# midithru.net
KiCad netlist of a schematic drawn in Altium Designer
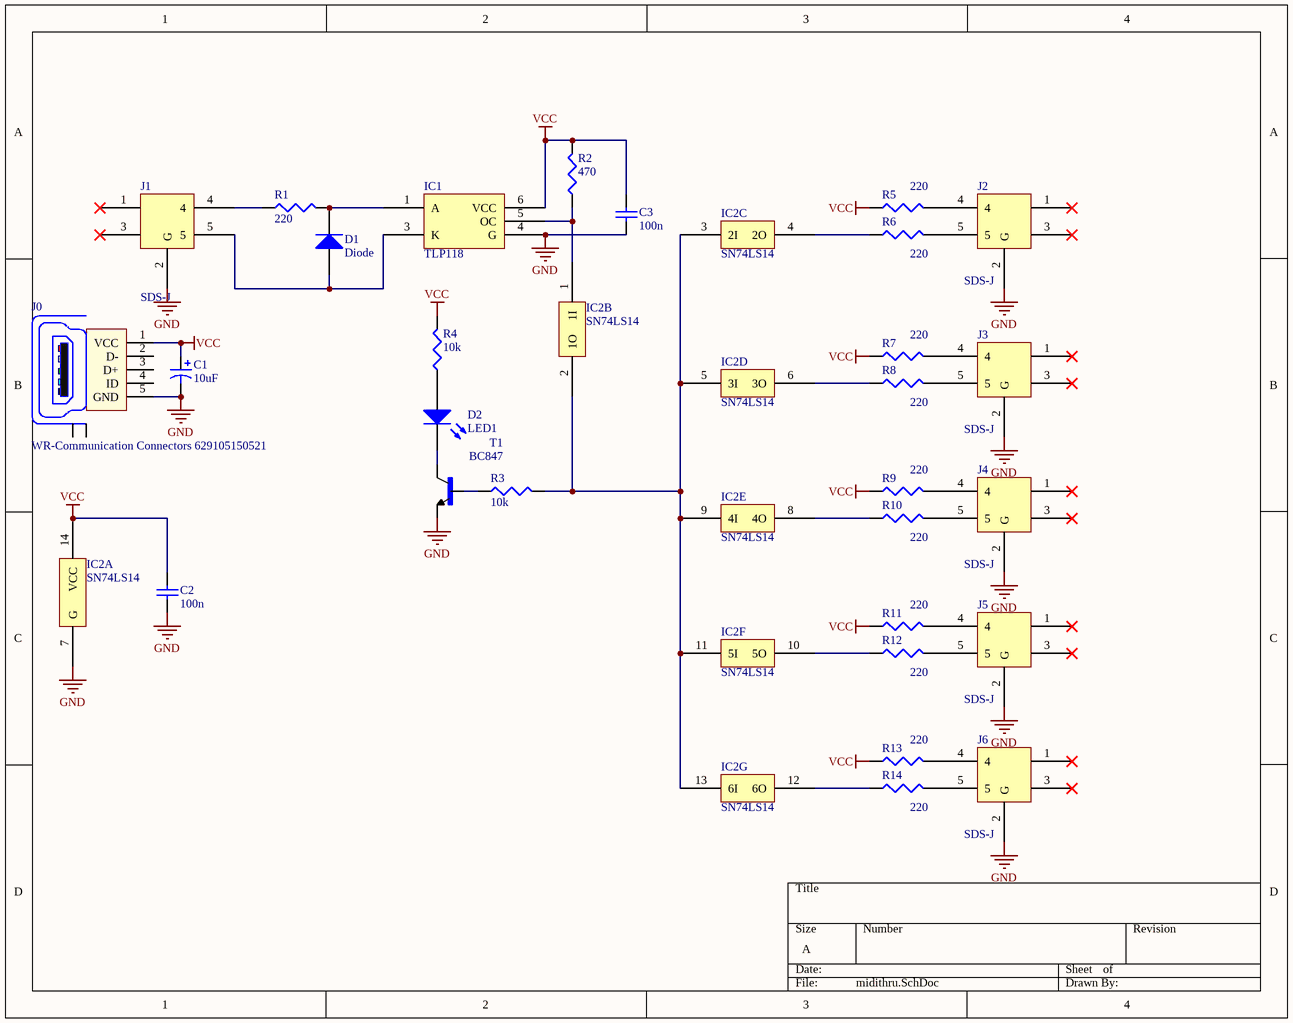
[diagram p0: midithru.SchDoc]

(export (version "E")
  (design (tool "Eeschema 10.0.6"))
  (components
    (comp (ref "C1")
      (value "10uF")
      (footprint "1210")
      (description "Polarized Capacitor (Surface Mount)")
      (fields (field (name "PUBLISHER") "Altium Limited"))
      (libsource (lib "Miscellaneous Devices") (part "Cap Pol3"))
    )
    (comp (ref "C2")
      (value "100n")
      (footprint "0805")
      (description "Capacitor (Semiconductor SIM Model)")
      (fields (field (name "PUBLISHER") "Altium Limited"))
      (libsource (lib "Miscellaneous Devices") (part "Cap Semi"))
    )
    (comp (ref "C3")
      (value "100n")
      (footprint "0805")
      (description "Capacitor (Semiconductor SIM Model)")
      (fields (field (name "PUBLISHER") "Altium Limited"))
      (libsource (lib "Miscellaneous Devices") (part "Cap Semi"))
    )
    (comp (ref "D1")
      (value "Diode")
      (footprint "0805")
      (description "Default Diode")
      (fields (field (name "PUBLISHER") "Altium Limited"))
      (libsource (lib "Miscellaneous Devices") (part "Diode"))
    )
    (comp (ref "D2")
      (value "LED1")
      (footprint "3.2X1.6X1.1")
      (description "Typical RED, GREEN, YELLOW, AMBER GaAs LED")
      (fields (field (name "PUBLISHER") "Altium Limited"))
      (libsource (lib "Miscellaneous Devices") (part "LED2"))
    )
    (comp (ref "IC1") (value "TLP118") (footprint "SOIC6") (libsource (lib "schlib") (part "TLP118")))
    (comp (ref "IC2") (value "SN74LS14") (footprint "SOIC14") (libsource (lib "schlib") (part "SN74LS14")))
    (comp (ref "J0")
      (value "WR-Communication Connectors 629105150521")
      (footprint "629105150521")
      (description "WR-COM_USB_Micro Type B_Horizontal_SMT")
      (fields
        (field (name "MANUFACTURER") "Würth Elektronik eiSos GmbH")
        (field (name "PARTNO") "629105150521")
        (field (name "CREATED BY") "Karrer Zheng")
      )
      (libsource (lib "629105136821 (rev16d)") (part "WR-Communication Connectors 629105150521"))
    )
    (comp (ref "J1") (value "SDS-J") (footprint "SDS-J") (libsource (lib "") (part "SDS-J_1")))
    (comp (ref "J2") (value "SDS-J") (footprint "SDS-J") (libsource (lib "schlib") (part "SDS-J")))
    (comp (ref "J3") (value "SDS-J") (footprint "SDS-J") (libsource (lib "schlib") (part "SDS-J")))
    (comp (ref "J4") (value "SDS-J") (footprint "SDS-J") (libsource (lib "schlib") (part "SDS-J")))
    (comp (ref "J5") (value "SDS-J") (footprint "SDS-J") (libsource (lib "schlib") (part "SDS-J")))
    (comp (ref "J6") (value "SDS-J") (footprint "SDS-J") (libsource (lib "schlib") (part "SDS-J")))
    (comp (ref "R1")
      (value "220")
      (footprint "0805")
      (description "Resistor")
      (fields (field (name "PUBLISHER") "Altium Limited"))
      (libsource (lib "Miscellaneous Devices") (part "Res3"))
    )
    (comp (ref "R2")
      (value "470")
      (footprint "0805")
      (description "Resistor")
      (fields (field (name "PUBLISHER") "Altium Limited"))
      (libsource (lib "Miscellaneous Devices") (part "Res3"))
    )
    (comp (ref "R3")
      (value "10k")
      (footprint "0805")
      (description "Resistor")
      (fields (field (name "PUBLISHER") "Altium Limited"))
      (libsource (lib "Miscellaneous Devices") (part "Res3"))
    )
    (comp (ref "R4")
      (value "10k")
      (footprint "0805")
      (description "Resistor")
      (fields (field (name "PUBLISHER") "Altium Limited"))
      (libsource (lib "Miscellaneous Devices") (part "Res3"))
    )
    (comp (ref "R5")
      (value "220")
      (footprint "0805")
      (description "Resistor")
      (fields (field (name "PUBLISHER") "Altium Limited"))
      (libsource (lib "Miscellaneous Devices") (part "Res3"))
    )
    (comp (ref "R6")
      (value "220")
      (footprint "0805")
      (description "Resistor")
      (fields (field (name "PUBLISHER") "Altium Limited"))
      (libsource (lib "Miscellaneous Devices") (part "Res3"))
    )
    (comp (ref "R7")
      (value "220")
      (footprint "0805")
      (description "Resistor")
      (fields (field (name "PUBLISHER") "Altium Limited"))
      (libsource (lib "Miscellaneous Devices") (part "Res3"))
    )
    (comp (ref "R8")
      (value "220")
      (footprint "0805")
      (description "Resistor")
      (fields (field (name "PUBLISHER") "Altium Limited"))
      (libsource (lib "Miscellaneous Devices") (part "Res3"))
    )
    (comp (ref "R9")
      (value "220")
      (footprint "0805")
      (description "Resistor")
      (fields (field (name "PUBLISHER") "Altium Limited"))
      (libsource (lib "Miscellaneous Devices") (part "Res3"))
    )
    (comp (ref "R10")
      (value "220")
      (footprint "0805")
      (description "Resistor")
      (fields (field (name "PUBLISHER") "Altium Limited"))
      (libsource (lib "Miscellaneous Devices") (part "Res3"))
    )
    (comp (ref "R11")
      (value "220")
      (footprint "0805")
      (description "Resistor")
      (fields (field (name "PUBLISHER") "Altium Limited"))
      (libsource (lib "Miscellaneous Devices") (part "Res3"))
    )
    (comp (ref "R12")
      (value "220")
      (footprint "0805")
      (description "Resistor")
      (fields (field (name "PUBLISHER") "Altium Limited"))
      (libsource (lib "Miscellaneous Devices") (part "Res3"))
    )
    (comp (ref "R13")
      (value "220")
      (footprint "0805")
      (description "Resistor")
      (fields (field (name "PUBLISHER") "Altium Limited"))
      (libsource (lib "Miscellaneous Devices") (part "Res3"))
    )
    (comp (ref "R14")
      (value "220")
      (footprint "0805")
      (description "Resistor")
      (fields (field (name "PUBLISHER") "Altium Limited"))
      (libsource (lib "Miscellaneous Devices") (part "Res3"))
    )
    (comp (ref "T1")
      (value "BC847")
      (footprint "*SOT23")
      (fields (field (name "MF") "Nexperia USA"))
      (libsource (lib "BC847") (part "BC847"))
    )
  )
  (nets
    (net (code "1") (name "GND") (class "Default")
      (node (ref "C1") (pin "2") (pinfunction "2_2") (pintype "passive"))
      (node (ref "C2") (pin "2") (pinfunction "2_2") (pintype "passive"))
      (node (ref "C3") (pin "2") (pinfunction "2_2") (pintype "passive"))
      (node (ref "IC1") (pin "4") (pinfunction "G_4") (pintype "passive"))
      (node (ref "IC2") (pin "7") (pinfunction "G_7") (pintype "passive"))
      (node (ref "J0") (pin "5") (pinfunction "GND_5") (pintype "passive"))
      (node (ref "J1") (pin "2") (pinfunction "G_2") (pintype "passive"))
      (node (ref "J2") (pin "2") (pinfunction "G_2") (pintype "passive"))
      (node (ref "J3") (pin "2") (pinfunction "G_2") (pintype "passive"))
      (node (ref "J4") (pin "2") (pinfunction "G_2") (pintype "passive"))
      (node (ref "J5") (pin "2") (pinfunction "G_2") (pintype "passive"))
      (node (ref "J6") (pin "2") (pinfunction "G_2") (pintype "passive"))
      (node (ref "T1") (pin "2") (pinfunction "E_2") (pintype "passive"))
    )
    (net (code "2") (name "Net-(D1-A)") (class "Default")
      (node (ref "D1") (pin "1") (pinfunction "A_1") (pintype "passive"))
      (node (ref "IC1") (pin "3") (pinfunction "K_3") (pintype "passive"))
      (node (ref "J1") (pin "5") (pinfunction "5_5") (pintype "passive"))
    )
    (net (code "3") (name "Net-(D1-K)") (class "Default")
      (node (ref "D1") (pin "2") (pinfunction "K_2") (pintype "passive"))
      (node (ref "IC1") (pin "1") (pinfunction "A_1") (pintype "passive"))
      (node (ref "R1") (pin "2") (pinfunction "2_2") (pintype "passive"))
    )
    (net (code "4") (name "Net-(D2-A)") (class "Default")
      (node (ref "D2") (pin "1") (pinfunction "A_1") (pintype "passive"))
      (node (ref "R4") (pin "1") (pinfunction "1_1") (pintype "passive"))
    )
    (net (code "5") (name "Net-(D2-K)") (class "Default")
      (node (ref "D2") (pin "2") (pinfunction "K_2") (pintype "passive"))
      (node (ref "T1") (pin "3") (pinfunction "C_3") (pintype "passive"))
    )
    (net (code "6") (name "Net-(IC1-OC)") (class "Default")
      (node (ref "IC1") (pin "5") (pinfunction "OC_5") (pintype "passive"))
      (node (ref "IC2") (pin "1") (pinfunction "1I_1") (pintype "passive"))
      (node (ref "R2") (pin "1") (pinfunction "1_1") (pintype "passive"))
    )
    (net (code "7") (name "Net-(IC2B-1O)") (class "Default")
      (node (ref "IC2") (pin "11") (pinfunction "5I_11") (pintype "passive"))
      (node (ref "IC2") (pin "13") (pinfunction "6I_13") (pintype "passive"))
      (node (ref "IC2") (pin "2") (pinfunction "1O_2") (pintype "passive"))
      (node (ref "IC2") (pin "3") (pinfunction "2I_3") (pintype "passive"))
      (node (ref "IC2") (pin "5") (pinfunction "3I_5") (pintype "passive"))
      (node (ref "IC2") (pin "9") (pinfunction "4I_9") (pintype "passive"))
      (node (ref "R3") (pin "2") (pinfunction "2_2") (pintype "passive"))
    )
    (net (code "8") (name "Net-(IC2C-2O)") (class "Default")
      (node (ref "IC2") (pin "4") (pinfunction "2O_4") (pintype "passive"))
      (node (ref "R6") (pin "1") (pinfunction "1_1") (pintype "passive"))
    )
    (net (code "9") (name "Net-(IC2D-3O)") (class "Default")
      (node (ref "IC2") (pin "6") (pinfunction "3O_6") (pintype "passive"))
      (node (ref "R8") (pin "1") (pinfunction "1_1") (pintype "passive"))
    )
    (net (code "10") (name "Net-(IC2E-4O)") (class "Default")
      (node (ref "IC2") (pin "8") (pinfunction "4O_8") (pintype "passive"))
      (node (ref "R10") (pin "1") (pinfunction "1_1") (pintype "passive"))
    )
    (net (code "11") (name "Net-(IC2F-5O)") (class "Default")
      (node (ref "IC2") (pin "10") (pinfunction "5O_10") (pintype "passive"))
      (node (ref "R12") (pin "1") (pinfunction "1_1") (pintype "passive"))
    )
    (net (code "12") (name "Net-(IC2G-6O)") (class "Default")
      (node (ref "IC2") (pin "12") (pinfunction "6O_12") (pintype "passive"))
      (node (ref "R14") (pin "1") (pinfunction "1_1") (pintype "passive"))
    )
    (net (code "13") (name "Net-(J1-Pad4)") (class "Default")
      (node (ref "J1") (pin "4") (pinfunction "4_4") (pintype "passive"))
      (node (ref "R1") (pin "1") (pinfunction "1_1") (pintype "passive"))
    )
    (net (code "14") (name "Net-(J2-Pad4)") (class "Default")
      (node (ref "J2") (pin "4") (pinfunction "4_4") (pintype "passive"))
      (node (ref "R5") (pin "2") (pinfunction "2_2") (pintype "passive"))
    )
    (net (code "15") (name "Net-(J2-Pad5)") (class "Default")
      (node (ref "J2") (pin "5") (pinfunction "5_5") (pintype "passive"))
      (node (ref "R6") (pin "2") (pinfunction "2_2") (pintype "passive"))
    )
    (net (code "16") (name "Net-(J3-Pad4)") (class "Default")
      (node (ref "J3") (pin "4") (pinfunction "4_4") (pintype "passive"))
      (node (ref "R7") (pin "2") (pinfunction "2_2") (pintype "passive"))
    )
    (net (code "17") (name "Net-(J3-Pad5)") (class "Default")
      (node (ref "J3") (pin "5") (pinfunction "5_5") (pintype "passive"))
      (node (ref "R8") (pin "2") (pinfunction "2_2") (pintype "passive"))
    )
    (net (code "18") (name "Net-(J4-Pad4)") (class "Default")
      (node (ref "J4") (pin "4") (pinfunction "4_4") (pintype "passive"))
      (node (ref "R9") (pin "2") (pinfunction "2_2") (pintype "passive"))
    )
    (net (code "19") (name "Net-(J4-Pad5)") (class "Default")
      (node (ref "J4") (pin "5") (pinfunction "5_5") (pintype "passive"))
      (node (ref "R10") (pin "2") (pinfunction "2_2") (pintype "passive"))
    )
    (net (code "20") (name "Net-(J5-Pad4)") (class "Default")
      (node (ref "J5") (pin "4") (pinfunction "4_4") (pintype "passive"))
      (node (ref "R11") (pin "2") (pinfunction "2_2") (pintype "passive"))
    )
    (net (code "21") (name "Net-(J5-Pad5)") (class "Default")
      (node (ref "J5") (pin "5") (pinfunction "5_5") (pintype "passive"))
      (node (ref "R12") (pin "2") (pinfunction "2_2") (pintype "passive"))
    )
    (net (code "22") (name "Net-(J6-Pad4)") (class "Default")
      (node (ref "J6") (pin "4") (pinfunction "4_4") (pintype "passive"))
      (node (ref "R13") (pin "2") (pinfunction "2_2") (pintype "passive"))
    )
    (net (code "23") (name "Net-(J6-Pad5)") (class "Default")
      (node (ref "J6") (pin "5") (pinfunction "5_5") (pintype "passive"))
      (node (ref "R14") (pin "2") (pinfunction "2_2") (pintype "passive"))
    )
    (net (code "24") (name "Net-(T1-B)") (class "Default")
      (node (ref "R3") (pin "1") (pinfunction "1_1") (pintype "passive"))
      (node (ref "T1") (pin "1") (pinfunction "B_1") (pintype "passive"))
    )
    (net (code "25") (name "VCC") (class "Default")
      (node (ref "C1") (pin "1") (pinfunction "1_1") (pintype "passive"))
      (node (ref "C2") (pin "1") (pinfunction "1_1") (pintype "passive"))
      (node (ref "C3") (pin "1") (pinfunction "1_1") (pintype "passive"))
      (node (ref "IC1") (pin "6") (pinfunction "VCC_6") (pintype "passive"))
      (node (ref "IC2") (pin "14") (pinfunction "VCC_14") (pintype "passive"))
      (node (ref "J0") (pin "1") (pinfunction "VCC_1") (pintype "passive"))
      (node (ref "R11") (pin "1") (pinfunction "1_1") (pintype "passive"))
      (node (ref "R13") (pin "1") (pinfunction "1_1") (pintype "passive"))
      (node (ref "R2") (pin "2") (pinfunction "2_2") (pintype "passive"))
      (node (ref "R4") (pin "2") (pinfunction "2_2") (pintype "passive"))
      (node (ref "R5") (pin "1") (pinfunction "1_1") (pintype "passive"))
      (node (ref "R7") (pin "1") (pinfunction "1_1") (pintype "passive"))
      (node (ref "R9") (pin "1") (pinfunction "1_1") (pintype "passive"))
    )
    (net (code "26") (name "unconnected-(J0-D+-Pad3)") (class "Default")
      (node (ref "J0") (pin "3") (pinfunction "D+_3") (pintype "passive"))
    )
    (net (code "27") (name "unconnected-(J0-D--Pad2)") (class "Default")
      (node (ref "J0") (pin "2") (pinfunction "D-_2") (pintype "passive"))
    )
    (net (code "28") (name "unconnected-(J0-ID-Pad4)") (class "Default")
      (node (ref "J0") (pin "4") (pinfunction "ID_4") (pintype "passive"))
    )
    (net (code "29") (name "unconnected-(J0-Shield-PadZ1)") (class "Default")
      (node (ref "J0") (pin "Z1") (pinfunction "Shield_Z1") (pintype "passive"))
    )
    (net (code "30") (name "unconnected-(J0-Shield-PadZ2)") (class "Default")
      (node (ref "J0") (pin "Z2") (pinfunction "Shield_Z2") (pintype "passive"))
    )
    (net (code "31") (name "unconnected-(J1-Pad1)") (class "Default")
      (node (ref "J1") (pin "1") (pinfunction "1_1") (pintype "passive+no_connect"))
    )
    (net (code "32") (name "unconnected-(J1-Pad3)") (class "Default")
      (node (ref "J1") (pin "3") (pinfunction "3_3") (pintype "passive+no_connect"))
    )
    (net (code "33") (name "unconnected-(J2-Pad1)") (class "Default")
      (node (ref "J2") (pin "1") (pinfunction "1_1") (pintype "passive+no_connect"))
    )
    (net (code "34") (name "unconnected-(J2-Pad3)") (class "Default")
      (node (ref "J2") (pin "3") (pinfunction "3_3") (pintype "passive+no_connect"))
    )
    (net (code "35") (name "unconnected-(J3-Pad1)") (class "Default")
      (node (ref "J3") (pin "1") (pinfunction "1_1") (pintype "passive+no_connect"))
    )
    (net (code "36") (name "unconnected-(J3-Pad3)") (class "Default")
      (node (ref "J3") (pin "3") (pinfunction "3_3") (pintype "passive+no_connect"))
    )
    (net (code "37") (name "unconnected-(J4-Pad1)") (class "Default")
      (node (ref "J4") (pin "1") (pinfunction "1_1") (pintype "passive+no_connect"))
    )
    (net (code "38") (name "unconnected-(J4-Pad3)") (class "Default")
      (node (ref "J4") (pin "3") (pinfunction "3_3") (pintype "passive+no_connect"))
    )
    (net (code "39") (name "unconnected-(J5-Pad1)") (class "Default")
      (node (ref "J5") (pin "1") (pinfunction "1_1") (pintype "passive+no_connect"))
    )
    (net (code "40") (name "unconnected-(J5-Pad3)") (class "Default")
      (node (ref "J5") (pin "3") (pinfunction "3_3") (pintype "passive+no_connect"))
    )
    (net (code "41") (name "unconnected-(J6-Pad1)") (class "Default")
      (node (ref "J6") (pin "1") (pinfunction "1_1") (pintype "passive+no_connect"))
    )
    (net (code "42") (name "unconnected-(J6-Pad3)") (class "Default")
      (node (ref "J6") (pin "3") (pinfunction "3_3") (pintype "passive+no_connect"))
    )
  )
)
